# LPC82X_TSSOP_breadboard.net
KiCad netlist of a schematic drawn in EAGLE
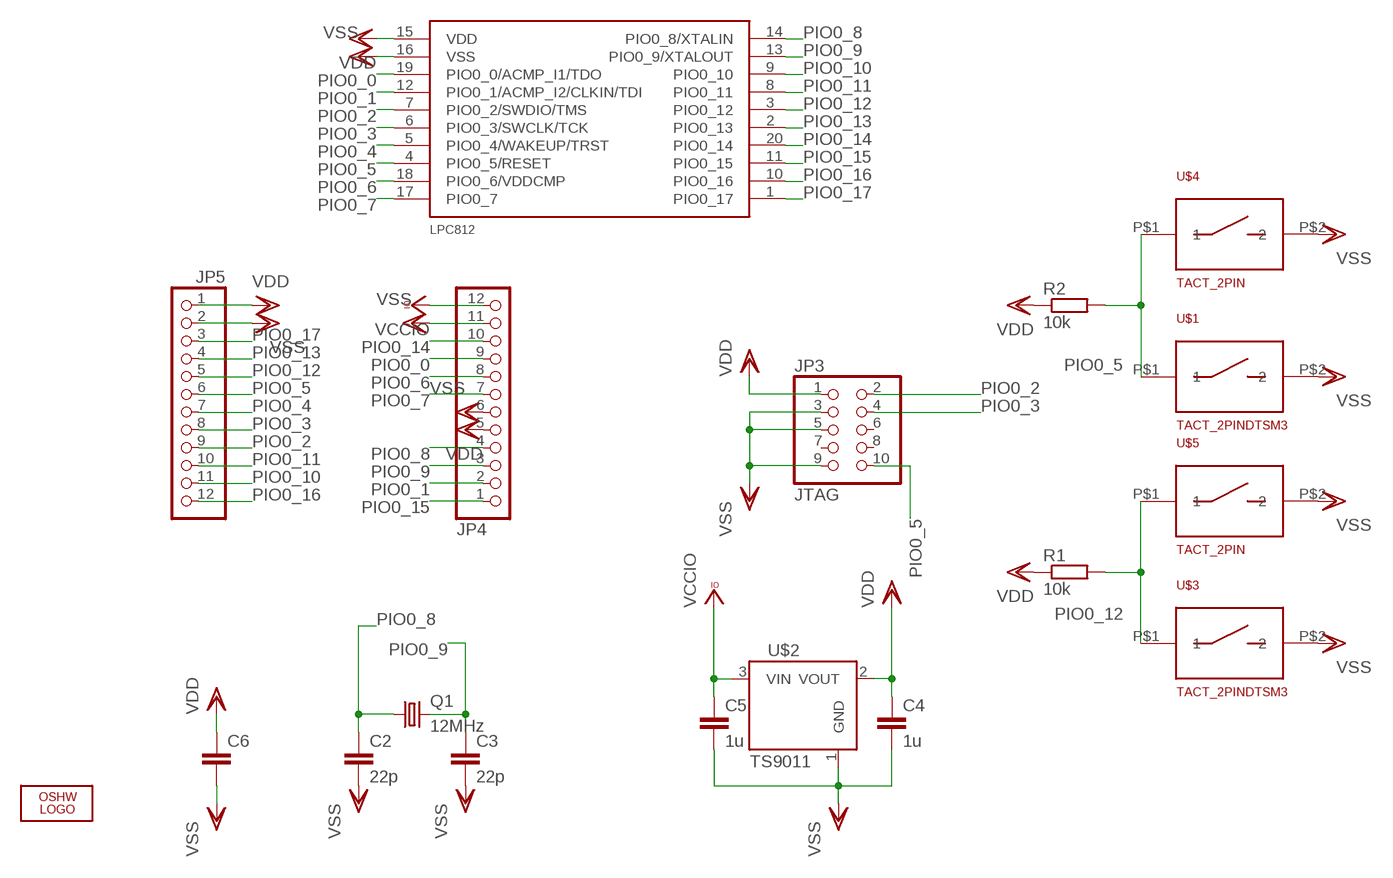
[diagram p0: schematic, sheet 1]

(export (version "E")
  (design (tool "Eeschema 10.0.6"))
  (components
    (comp (ref "C2")
      (value "22p")
      (footprint "eagle-import:C0603K")
      (libsource (lib "eagle-import") (part "C-EUC0603K"))
    )
    (comp (ref "C3")
      (value "22p")
      (footprint "eagle-import:C0603K")
      (libsource (lib "eagle-import") (part "C-EUC0603K"))
    )
    (comp (ref "C4")
      (value "1u")
      (footprint "eagle-import:C0805K")
      (libsource (lib "eagle-import") (part "bart_rcl_C-EUC0805K"))
    )
    (comp (ref "C5")
      (value "1u")
      (footprint "eagle-import:C0805K")
      (libsource (lib "eagle-import") (part "bart_rcl_C-EUC0805K"))
    )
    (comp (ref "C6")
      (value "C-EUC0603K")
      (footprint "eagle-import:C0603K")
      (libsource (lib "eagle-import") (part "C-EUC0603K"))
    )
    (comp (ref "JP3")
      (value "JTAG")
      (footprint "eagle-import:2X05_1.27_SMD")
      (libsource (lib "eagle-import") (part "PINHD-2X5SMD_1.27_SMD"))
    )
    (comp (ref "JP4")
      (value "PINHD-1X12NORM_OCT")
      (footprint "eagle-import:1X12_NORMAL_OCT")
      (libsource (lib "eagle-import") (part "PINHD-1X12NORM_OCT"))
    )
    (comp (ref "JP5")
      (value "PINHD-1X12NORM_OCT")
      (footprint "eagle-import:1X12_NORMAL_OCT")
      (libsource (lib "eagle-import") (part "PINHD-1X12NORM_OCT"))
    )
    (comp (ref "LOGO2")
      (value "OSHW_LOGO_FILLX0150-NT")
      (footprint "eagle-import:OSHW_FILLX150_NOTEXT")
      (libsource (lib "eagle-import") (part "OSHW_LOGO_FILLX0150-NT"))
    )
    (comp (ref "LPC812")
      (value "LPC812M101JDH20")
      (footprint "eagle-import:TSSOP20")
      (libsource (lib "eagle-import") (part "LPC812M101JDH20"))
    )
    (comp (ref "Q1")
      (value "12MHz")
      (footprint "eagle-import:CRYSTAL_5.0X3.2")
      (libsource (lib "eagle-import") (part "CRYSTALSMD_5.0X3.2"))
    )
    (comp (ref "R1")
      (value "10k")
      (footprint "eagle-import:R0603")
      (libsource (lib "eagle-import") (part "R-EU_R0603"))
    )
    (comp (ref "R2")
      (value "10k")
      (footprint "eagle-import:R0603")
      (libsource (lib "eagle-import") (part "R-EU_R0603"))
    )
    (comp (ref "U$1")
      (value "TACT_2PINDTSM3")
      (footprint "eagle-import:DTSM3")
      (libsource (lib "eagle-import") (part "TACT_2PINDTSM3"))
    )
    (comp (ref "U$2")
      (value "TS9011")
      (footprint "eagle-import:SOT23-3")
      (libsource (lib "eagle-import") (part "TS9011"))
    )
    (comp (ref "U$3")
      (value "TACT_2PINDTSM3")
      (footprint "eagle-import:DTSM3")
      (libsource (lib "eagle-import") (part "TACT_2PINDTSM3"))
    )
    (comp (ref "U$4")
      (value "TACT_2PIN")
      (footprint "eagle-import:TD-85XU")
      (libsource (lib "eagle-import") (part "TACT_2PIN"))
    )
    (comp (ref "U$5")
      (value "TACT_2PIN")
      (footprint "eagle-import:TD-85XU")
      (libsource (lib "eagle-import") (part "TACT_2PIN"))
    )
  )
  (nets
    (net (code "1") (name "/PIO0_0") (class "Default")
      (node (ref "JP4") (pin "9") (pinfunction "9_9") (pintype "passive"))
      (node (ref "LPC812") (pin "19") (pinfunction "PIO0_0/ACMP_I1/TDO_19") (pintype "bidirectional"))
    )
    (net (code "2") (name "/PIO0_1") (class "Default")
      (node (ref "JP4") (pin "2") (pinfunction "2_2") (pintype "passive"))
      (node (ref "LPC812") (pin "12") (pinfunction "PIO0_1/ACMP_I2/CLKIN/TDI_12") (pintype "bidirectional"))
    )
    (net (code "3") (name "/PIO0_2") (class "Default")
      (node (ref "JP3") (pin "2") (pinfunction "2_2") (pintype "passive"))
      (node (ref "JP5") (pin "9") (pinfunction "9_9") (pintype "passive"))
      (node (ref "LPC812") (pin "7") (pinfunction "PIO0_2/SWDIO/TMS_7") (pintype "bidirectional"))
    )
    (net (code "4") (name "/PIO0_3") (class "Default")
      (node (ref "JP3") (pin "4") (pinfunction "4_4") (pintype "passive"))
      (node (ref "JP5") (pin "8") (pinfunction "8_8") (pintype "passive"))
      (node (ref "LPC812") (pin "6") (pinfunction "PIO0_3/SWCLK/TCK_6") (pintype "bidirectional"))
    )
    (net (code "5") (name "/PIO0_4") (class "Default")
      (node (ref "JP5") (pin "7") (pinfunction "7_7") (pintype "passive"))
      (node (ref "LPC812") (pin "5") (pinfunction "PIO0_4/WAKEUP/TRST_5") (pintype "bidirectional"))
    )
    (net (code "6") (name "/PIO0_5") (class "Default")
      (node (ref "JP3") (pin "10") (pinfunction "10_10") (pintype "passive"))
      (node (ref "JP5") (pin "6") (pinfunction "6_6") (pintype "passive"))
      (node (ref "LPC812") (pin "4") (pinfunction "PIO0_5/RESET_4") (pintype "bidirectional"))
      (node (ref "R2") (pin "2") (pinfunction "2_2") (pintype "passive"))
      (node (ref "U$1") (pin "P$1") (pinfunction "1_P$1") (pintype "bidirectional"))
      (node (ref "U$4") (pin "P$1") (pinfunction "1_P$1") (pintype "bidirectional"))
    )
    (net (code "7") (name "/PIO0_6") (class "Default")
      (node (ref "JP4") (pin "8") (pinfunction "8_8") (pintype "passive"))
      (node (ref "LPC812") (pin "18") (pinfunction "PIO0_6/VDDCMP_18") (pintype "bidirectional"))
    )
    (net (code "8") (name "/PIO0_7") (class "Default")
      (node (ref "JP4") (pin "7") (pinfunction "7_7") (pintype "passive"))
      (node (ref "LPC812") (pin "17") (pinfunction "PIO0_7_17") (pintype "bidirectional"))
    )
    (net (code "9") (name "/PIO0_8") (class "Default")
      (node (ref "C2") (pin "1") (pinfunction "1_1") (pintype "passive"))
      (node (ref "JP4") (pin "4") (pinfunction "4_4") (pintype "passive"))
      (node (ref "LPC812") (pin "14") (pinfunction "PIO0_8/XTALIN_14") (pintype "bidirectional"))
      (node (ref "Q1") (pin "1") (pinfunction "1_1") (pintype "passive"))
    )
    (net (code "10") (name "/PIO0_9") (class "Default")
      (node (ref "C3") (pin "1") (pinfunction "1_1") (pintype "passive"))
      (node (ref "JP4") (pin "3") (pinfunction "3_3") (pintype "passive"))
      (node (ref "LPC812") (pin "13") (pinfunction "PIO0_9/XTALOUT_13") (pintype "bidirectional"))
      (node (ref "Q1") (pin "2") (pinfunction "2_2") (pintype "passive"))
    )
    (net (code "11") (name "/PIO0_10") (class "Default")
      (node (ref "JP5") (pin "11") (pinfunction "11_11") (pintype "passive"))
      (node (ref "LPC812") (pin "9") (pinfunction "PIO0_10_9") (pintype "bidirectional"))
    )
    (net (code "12") (name "/PIO0_11") (class "Default")
      (node (ref "JP5") (pin "10") (pinfunction "10_10") (pintype "passive"))
      (node (ref "LPC812") (pin "8") (pinfunction "PIO0_11_8") (pintype "bidirectional"))
    )
    (net (code "13") (name "/PIO0_12") (class "Default")
      (node (ref "JP5") (pin "5") (pinfunction "5_5") (pintype "passive"))
      (node (ref "LPC812") (pin "3") (pinfunction "PIO0_12_3") (pintype "bidirectional"))
      (node (ref "R1") (pin "2") (pinfunction "2_2") (pintype "passive"))
      (node (ref "U$3") (pin "P$1") (pinfunction "1_P$1") (pintype "bidirectional"))
      (node (ref "U$5") (pin "P$1") (pinfunction "1_P$1") (pintype "bidirectional"))
    )
    (net (code "14") (name "/PIO0_13") (class "Default")
      (node (ref "JP5") (pin "4") (pinfunction "4_4") (pintype "passive"))
      (node (ref "LPC812") (pin "2") (pinfunction "PIO0_13_2") (pintype "bidirectional"))
    )
    (net (code "15") (name "/PIO0_14") (class "Default")
      (node (ref "JP4") (pin "10") (pinfunction "10_10") (pintype "passive"))
      (node (ref "LPC812") (pin "20") (pinfunction "PIO0_14_20") (pintype "bidirectional"))
    )
    (net (code "16") (name "/PIO0_15") (class "Default")
      (node (ref "JP4") (pin "1") (pinfunction "1_1") (pintype "passive"))
      (node (ref "LPC812") (pin "11") (pinfunction "PIO0_15_11") (pintype "bidirectional"))
    )
    (net (code "17") (name "/PIO0_16") (class "Default")
      (node (ref "JP5") (pin "12") (pinfunction "12_12") (pintype "passive"))
      (node (ref "LPC812") (pin "10") (pinfunction "PIO0_16_10") (pintype "bidirectional"))
    )
    (net (code "18") (name "/PIO0_17") (class "Default")
      (node (ref "JP5") (pin "3") (pinfunction "3_3") (pintype "passive"))
      (node (ref "LPC812") (pin "1") (pinfunction "PIO0_17_1") (pintype "bidirectional"))
    )
    (net (code "19") (name "VCCIO") (class "Default")
      (node (ref "C5") (pin "1") (pinfunction "1_1") (pintype "passive"))
      (node (ref "JP4") (pin "12") (pinfunction "12_12") (pintype "passive"))
      (node (ref "U$2") (pin "3") (pinfunction "VIN_3") (pintype "bidirectional"))
    )
    (net (code "20") (name "VDD") (class "Default")
      (node (ref "C4") (pin "1") (pinfunction "1_1") (pintype "passive"))
      (node (ref "C6") (pin "1") (pinfunction "1_1") (pintype "passive"))
      (node (ref "JP3") (pin "1") (pinfunction "1_1") (pintype "passive"))
      (node (ref "JP4") (pin "5") (pinfunction "5_5") (pintype "passive"))
      (node (ref "JP5") (pin "1") (pinfunction "1_1") (pintype "passive"))
      (node (ref "LPC812") (pin "15") (pinfunction "VDD_15") (pintype "bidirectional"))
      (node (ref "R1") (pin "1") (pinfunction "1_1") (pintype "passive"))
      (node (ref "R2") (pin "1") (pinfunction "1_1") (pintype "passive"))
      (node (ref "U$2") (pin "2") (pinfunction "VOUT_2") (pintype "bidirectional"))
    )
    (net (code "21") (name "VSS") (class "Default")
      (node (ref "C2") (pin "2") (pinfunction "2_2") (pintype "passive"))
      (node (ref "C3") (pin "2") (pinfunction "2_2") (pintype "passive"))
      (node (ref "C4") (pin "2") (pinfunction "2_2") (pintype "passive"))
      (node (ref "C5") (pin "2") (pinfunction "2_2") (pintype "passive"))
      (node (ref "C6") (pin "2") (pinfunction "2_2") (pintype "passive"))
      (node (ref "JP3") (pin "3") (pinfunction "3_3") (pintype "passive"))
      (node (ref "JP3") (pin "5") (pinfunction "5_5") (pintype "passive"))
      (node (ref "JP3") (pin "9") (pinfunction "9_9") (pintype "passive"))
      (node (ref "JP4") (pin "11") (pinfunction "11_11") (pintype "passive"))
      (node (ref "JP4") (pin "6") (pinfunction "6_6") (pintype "passive"))
      (node (ref "JP5") (pin "2") (pinfunction "2_2") (pintype "passive"))
      (node (ref "LPC812") (pin "16") (pinfunction "VSS_16") (pintype "bidirectional"))
      (node (ref "U$1") (pin "P$2") (pinfunction "2_P$2") (pintype "bidirectional"))
      (node (ref "U$2") (pin "1") (pinfunction "GND_1") (pintype "bidirectional"))
      (node (ref "U$3") (pin "P$2") (pinfunction "2_P$2") (pintype "bidirectional"))
      (node (ref "U$4") (pin "P$2") (pinfunction "2_P$2") (pintype "bidirectional"))
      (node (ref "U$5") (pin "P$2") (pinfunction "2_P$2") (pintype "bidirectional"))
    )
    (net (code "22") (name "unconnected-(JP3-Pad6)") (class "Default")
      (node (ref "JP3") (pin "6") (pinfunction "6_6") (pintype "passive"))
    )
    (net (code "23") (name "unconnected-(JP3-Pad7)") (class "Default")
      (node (ref "JP3") (pin "7") (pinfunction "7_7") (pintype "passive"))
    )
    (net (code "24") (name "unconnected-(JP3-Pad8)") (class "Default")
      (node (ref "JP3") (pin "8") (pinfunction "8_8") (pintype "passive"))
    )
  )
)
